# TSOC_GROVEY_WIFI_R0_0.net
KiCad netlist of a schematic drawn in EAGLE
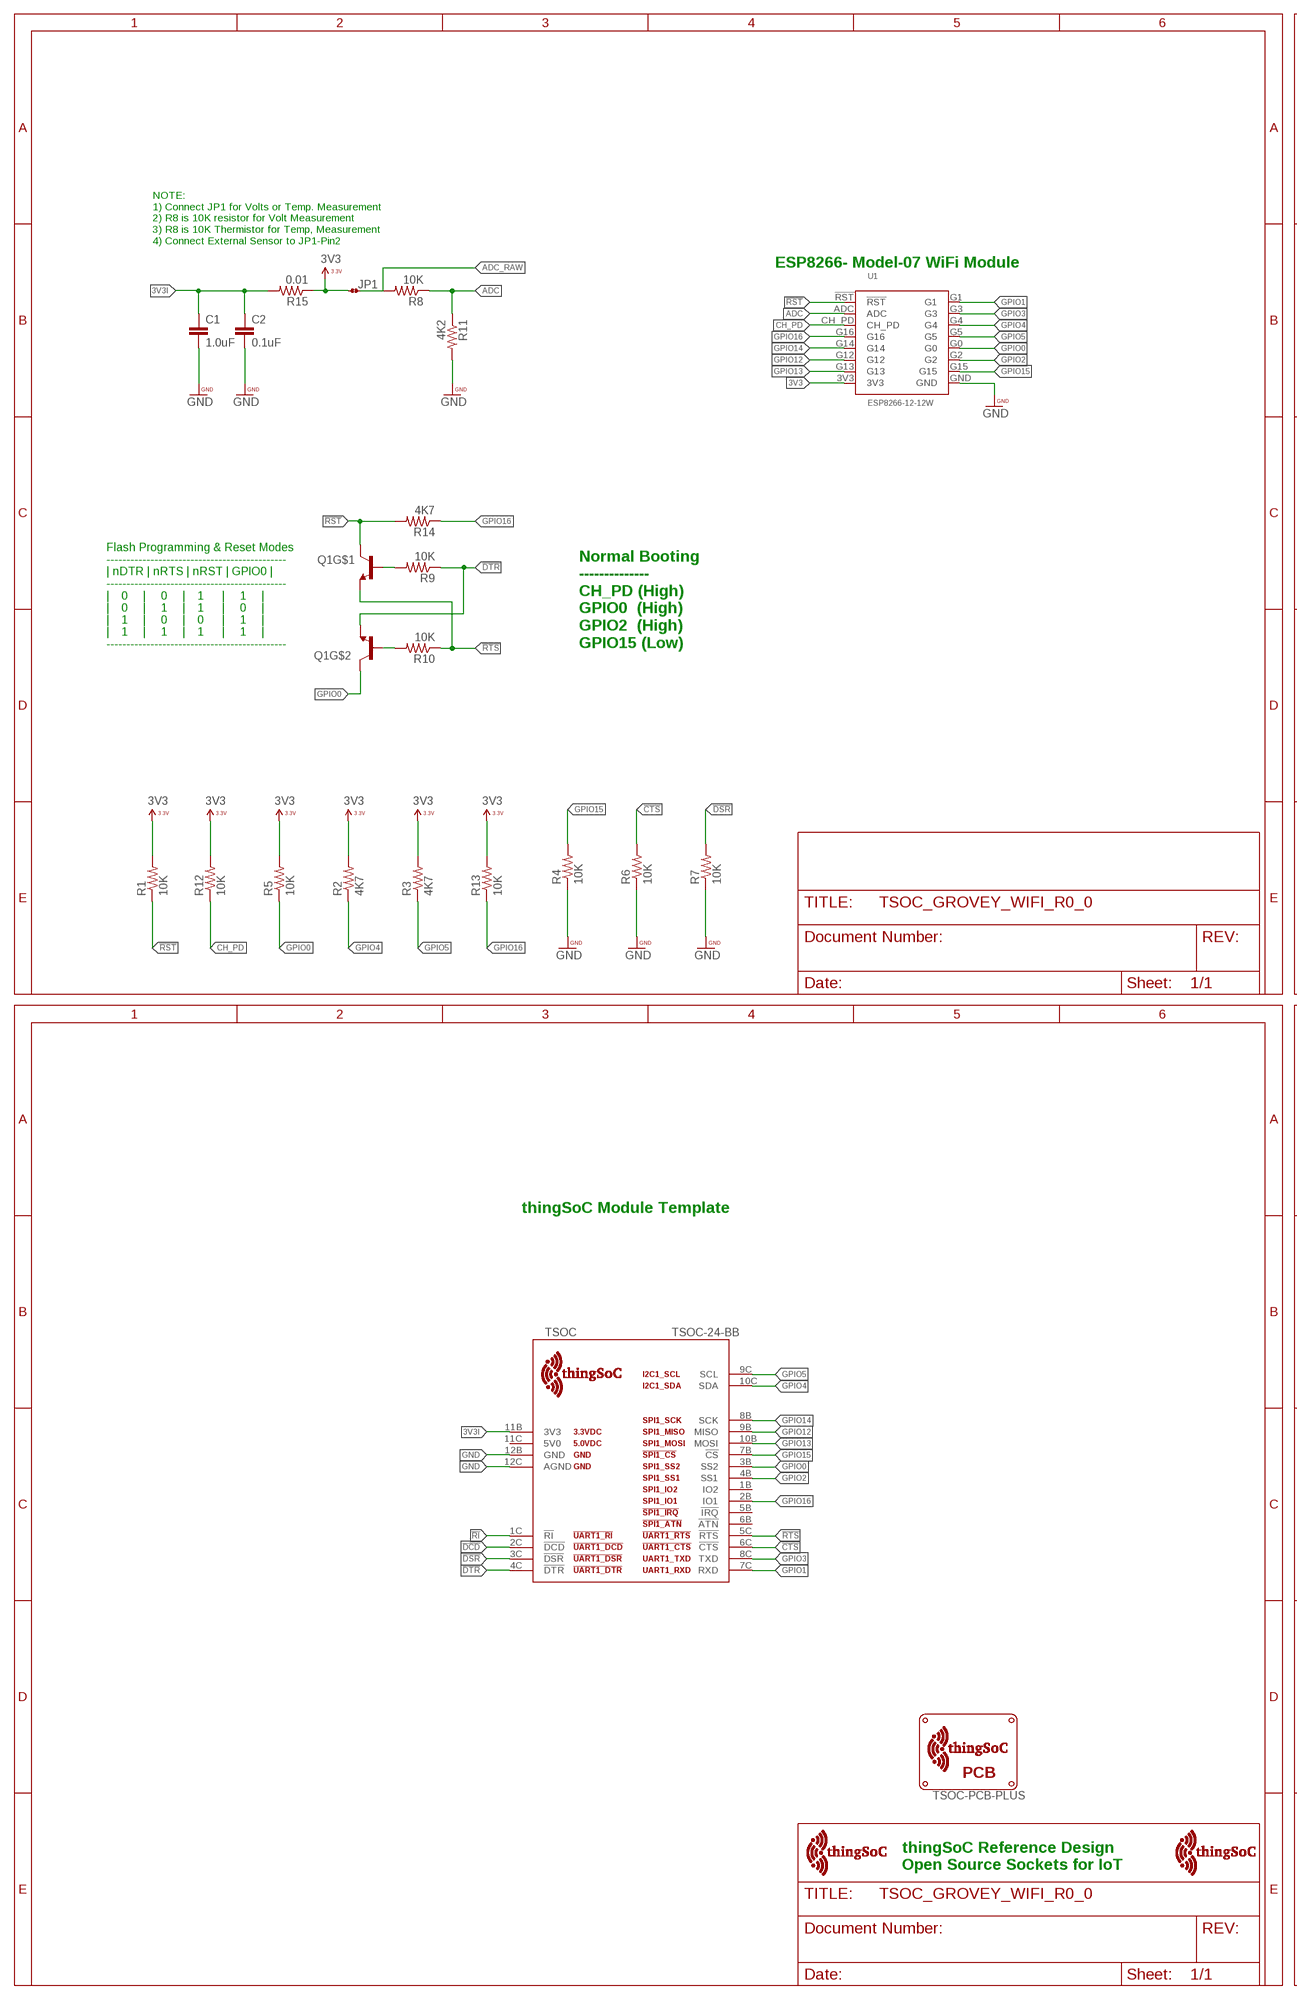
[diagram p0: schematic, sheet 1, part 1 of 2]
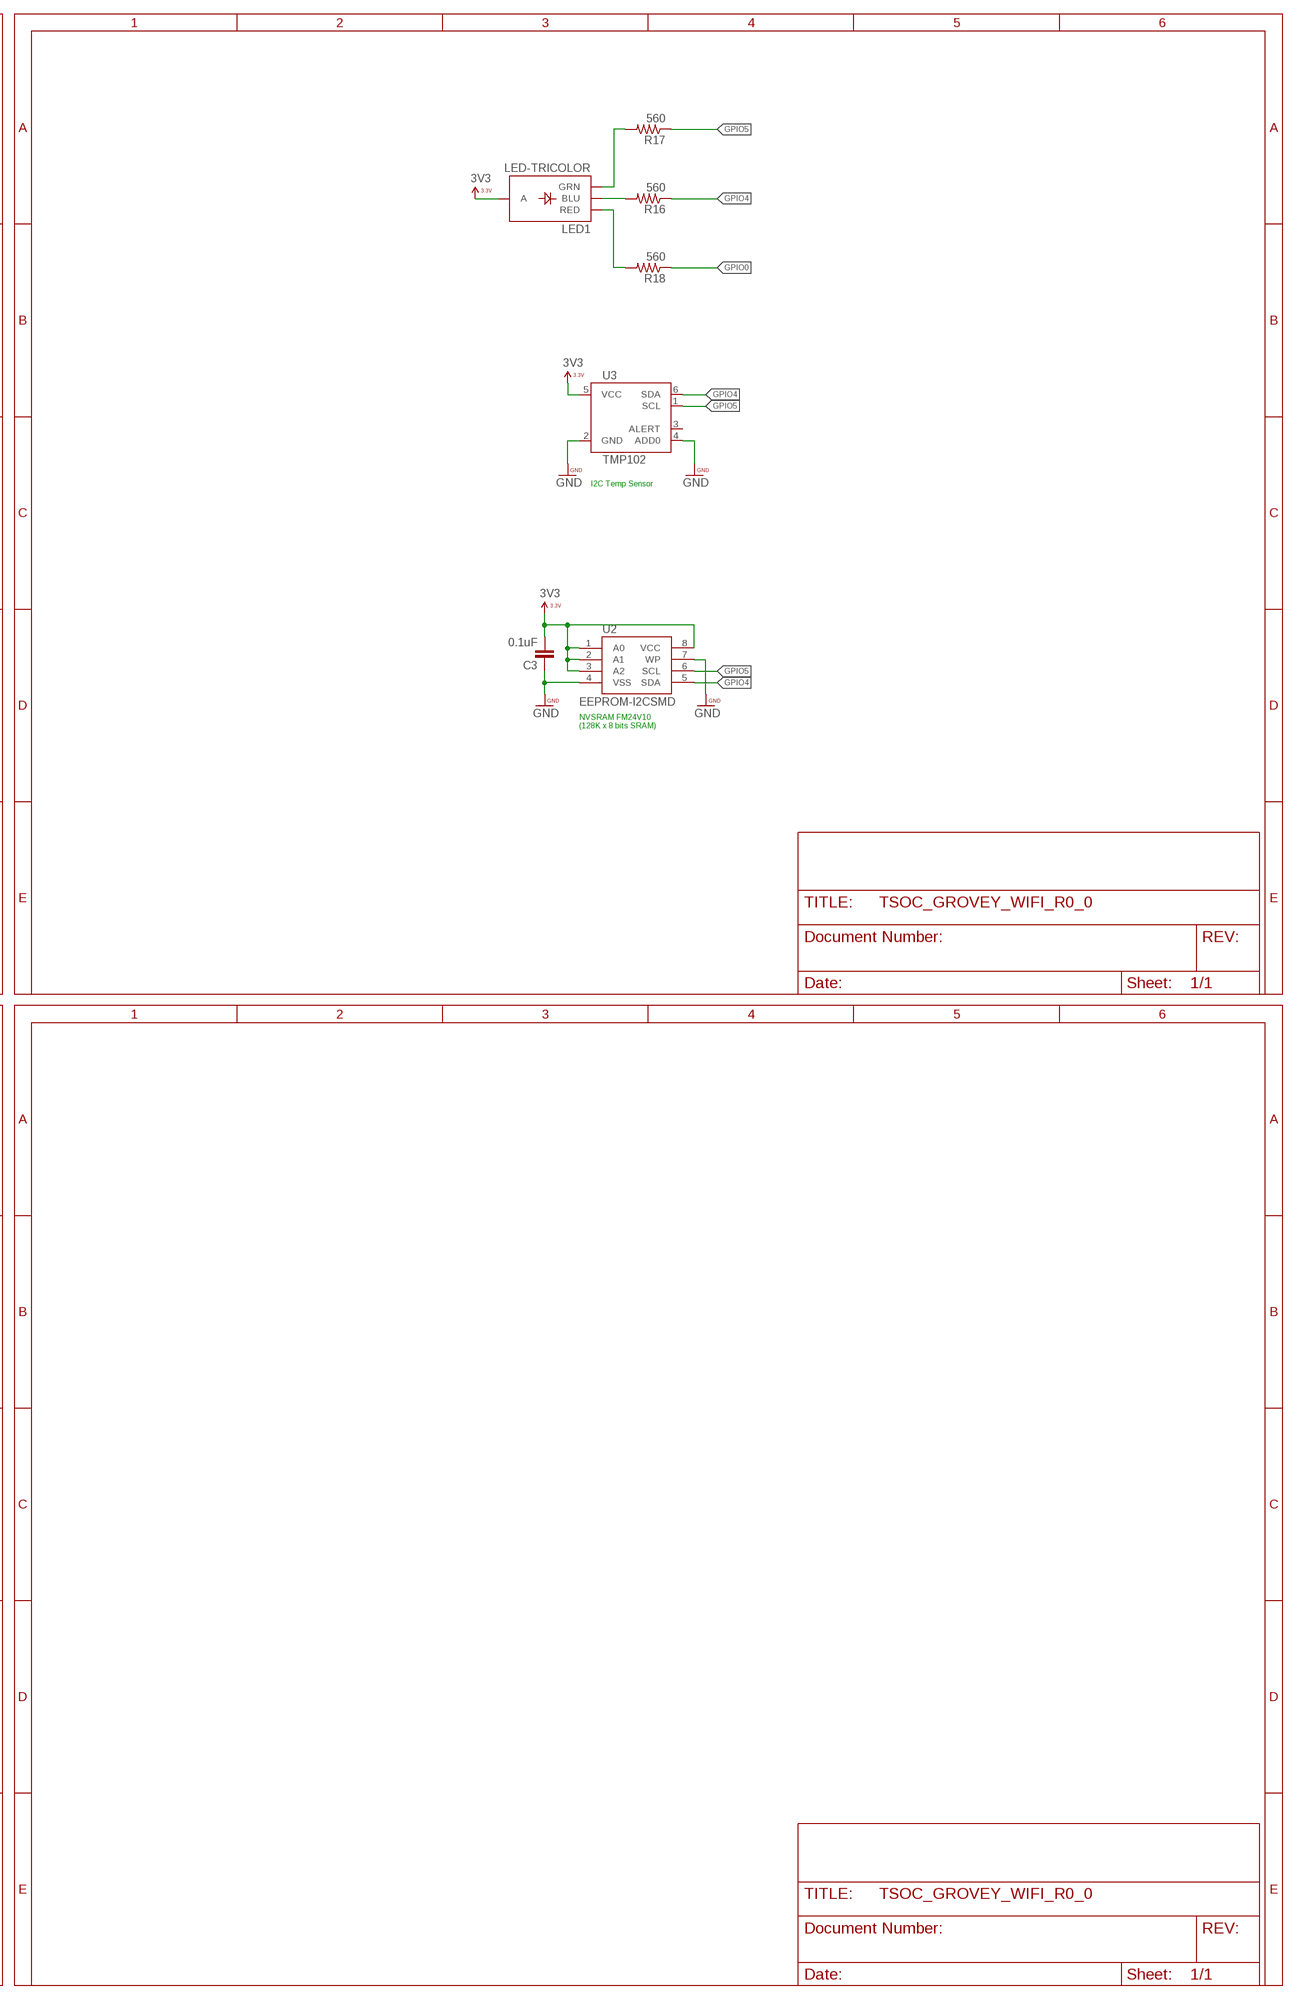
[diagram p1: schematic, sheet 1, part 2 of 2]

(export (version "E")
  (design (tool "Eeschema 10.0.6"))
  (components
    (comp (ref "C1")
      (value "1.0uF")
      (footprint "eagle-import:0402-CAP")
      (libsource (lib "eagle-import") (part "CAP0402-CAP"))
    )
    (comp (ref "C2")
      (value "0.1uF")
      (footprint "eagle-import:0402-CAP")
      (libsource (lib "eagle-import") (part "CAP0402-CAP"))
    )
    (comp (ref "C3")
      (value "0.1uF")
      (footprint "eagle-import:0402-CAP")
      (libsource (lib "eagle-import") (part "CAP0402-CAP"))
    )
    (comp (ref "JP1")
      (value "JMP-2-NO-0402")
      (footprint "eagle-import:JMP-2-NO-0402")
      (libsource (lib "eagle-import") (part "JMP-2-NO-0402"))
    )
    (comp (ref "LED1")
      (value "LED-TRICOLOR")
      (footprint "eagle-import:LED-TRICOLOR-SMD")
      (libsource (lib "eagle-import") (part "LED-TRICOLOR"))
    )
    (comp (ref "Q1")
      (value "MMBT2222A")
      (footprint "eagle-import:SOT363")
      (libsource (lib "eagle-import") (part "MMDT3904"))
    )
    (comp (ref "R1")
      (value "10K")
      (footprint "eagle-import:0402-RES")
      (libsource (lib "eagle-import") (part "RESISTOR0402"))
    )
    (comp (ref "R2")
      (value "4K7")
      (footprint "eagle-import:0402-RES")
      (libsource (lib "eagle-import") (part "RESISTOR0402"))
    )
    (comp (ref "R3")
      (value "4K7")
      (footprint "eagle-import:0402-RES")
      (libsource (lib "eagle-import") (part "RESISTOR0402"))
    )
    (comp (ref "R4")
      (value "10K")
      (footprint "eagle-import:0402-RES")
      (libsource (lib "eagle-import") (part "RESISTOR0402"))
    )
    (comp (ref "R5")
      (value "10K")
      (footprint "eagle-import:0402-RES")
      (libsource (lib "eagle-import") (part "RESISTOR0402"))
    )
    (comp (ref "R6")
      (value "10K")
      (footprint "eagle-import:0402-RES")
      (libsource (lib "eagle-import") (part "RESISTOR0402"))
    )
    (comp (ref "R7")
      (value "10K")
      (footprint "eagle-import:0402-RES")
      (libsource (lib "eagle-import") (part "RESISTOR0402"))
    )
    (comp (ref "R8")
      (value "10K")
      (footprint "eagle-import:0402-RES")
      (libsource (lib "eagle-import") (part "RESISTOR0402"))
    )
    (comp (ref "R9")
      (value "10K")
      (footprint "eagle-import:0402-RES")
      (libsource (lib "eagle-import") (part "RESISTOR0402"))
    )
    (comp (ref "R10")
      (value "10K")
      (footprint "eagle-import:0402-RES")
      (libsource (lib "eagle-import") (part "RESISTOR0402"))
    )
    (comp (ref "R11")
      (value "4K2")
      (footprint "eagle-import:0402-RES")
      (libsource (lib "eagle-import") (part "RESISTOR0402"))
    )
    (comp (ref "R12")
      (value "10K")
      (footprint "eagle-import:0402-RES")
      (libsource (lib "eagle-import") (part "RESISTOR0402"))
    )
    (comp (ref "R13")
      (value "10K")
      (footprint "eagle-import:0402-RES")
      (libsource (lib "eagle-import") (part "RESISTOR0402"))
    )
    (comp (ref "R14")
      (value "4K7")
      (footprint "eagle-import:0402-RES")
      (libsource (lib "eagle-import") (part "RESISTOR0402"))
    )
    (comp (ref "R15")
      (value "0.01")
      (footprint "eagle-import:0402-RES")
      (libsource (lib "eagle-import") (part "RESISTOR0402"))
    )
    (comp (ref "R16")
      (value "560")
      (footprint "eagle-import:0402-RES")
      (libsource (lib "eagle-import") (part "RESISTOR0402"))
    )
    (comp (ref "R17")
      (value "560")
      (footprint "eagle-import:0402-RES")
      (libsource (lib "eagle-import") (part "RESISTOR0402"))
    )
    (comp (ref "R18")
      (value "560")
      (footprint "eagle-import:0402-RES")
      (libsource (lib "eagle-import") (part "RESISTOR0402"))
    )
    (comp (ref "TSOC")
      (value "TSOC-24-BB")
      (footprint "eagle-import:TSOC-BB-S24")
      (libsource (lib "eagle-import") (part "TSOC-24-BB"))
    )
    (comp (ref "U$19")
      (value "TSOC-LOGO-MED")
      (footprint "eagle-import:TSOC-LOGO-MED")
      (libsource (lib "eagle-import") (part "TSOC-LOGO-MED"))
    )
    (comp (ref "U$20")
      (value "TSOC-LOGO-MED")
      (footprint "eagle-import:TSOC-LOGO-MED")
      (libsource (lib "eagle-import") (part "TSOC-LOGO-MED"))
    )
    (comp (ref "U$25")
      (value "TSOC-PCB-PLUS")
      (footprint "eagle-import:TSOC-BB-BRD-PLUS-DIM")
      (libsource (lib "eagle-import") (part "TSOC-PCB-PLUS"))
    )
    (comp (ref "U1")
      (value "ESP8266-12-12W")
      (footprint "eagle-import:ESP8266-12W")
      (libsource (lib "eagle-import") (part "ESP8266-12-12W"))
    )
    (comp (ref "U2")
      (value "EEPROM-I2CSMD")
      (footprint "eagle-import:SO08")
      (libsource (lib "eagle-import") (part "EEPROM-I2CSMD"))
    )
    (comp (ref "U3")
      (value "TMP102")
      (footprint "eagle-import:SOT563")
      (libsource (lib "eagle-import") (part "TMP102"))
    )
  )
  (nets
    (net (code "1") (name "/~{CTS}") (class "Default")
      (node (ref "R6") (pin "2") (pinfunction "2_2") (pintype "passive"))
      (node (ref "TSOC") (pin "6C") (pinfunction "~{CTS}_6C") (pintype "bidirectional"))
    )
    (net (code "2") (name "/~{DCD}") (class "Default")
      (node (ref "TSOC") (pin "2C") (pinfunction "~{DCD}_2C") (pintype "bidirectional"))
    )
    (net (code "3") (name "/~{DSR}") (class "Default")
      (node (ref "R7") (pin "2") (pinfunction "2_2") (pintype "passive"))
      (node (ref "TSOC") (pin "3C") (pinfunction "~{DSR}_3C") (pintype "bidirectional"))
    )
    (net (code "4") (name "/~{DTR}") (class "Default")
      (node (ref "Q1") (pin "1") (pinfunction "E_1") (pintype "passive"))
      (node (ref "R9") (pin "1") (pinfunction "1_1") (pintype "passive"))
      (node (ref "TSOC") (pin "4C") (pinfunction "~{DTR}_4C") (pintype "bidirectional"))
    )
    (net (code "5") (name "/~{RI}") (class "Default")
      (node (ref "TSOC") (pin "1C") (pinfunction "~{RI}_1C") (pintype "bidirectional"))
    )
    (net (code "6") (name "/~{RST}") (class "Default")
      (node (ref "Q1") (pin "3") (pinfunction "C_3") (pintype "passive"))
      (node (ref "R1") (pin "1") (pinfunction "1_1") (pintype "passive"))
      (node (ref "R14") (pin "2") (pinfunction "2_2") (pintype "passive"))
      (node (ref "U1") (pin "!RST") (pinfunction "~{RST}_!RST") (pintype "bidirectional"))
    )
    (net (code "7") (name "/~{RTS}") (class "Default")
      (node (ref "Q1") (pin "4") (pinfunction "E_4") (pintype "passive"))
      (node (ref "R10") (pin "1") (pinfunction "1_1") (pintype "passive"))
      (node (ref "TSOC") (pin "5C") (pinfunction "~{RTS}_5C") (pintype "bidirectional"))
    )
    (net (code "8") (name "3V3") (class "Default")
      (node (ref "C3") (pin "2") (pinfunction "2_2") (pintype "passive"))
      (node (ref "JP1") (pin "1") (pinfunction "1_1") (pintype "passive"))
      (node (ref "LED1") (pin "A") (pinfunction "A_A") (pintype "bidirectional"))
      (node (ref "R1") (pin "2") (pinfunction "2_2") (pintype "passive"))
      (node (ref "R12") (pin "2") (pinfunction "2_2") (pintype "passive"))
      (node (ref "R13") (pin "2") (pinfunction "2_2") (pintype "passive"))
      (node (ref "R15") (pin "1") (pinfunction "1_1") (pintype "passive"))
      (node (ref "R2") (pin "2") (pinfunction "2_2") (pintype "passive"))
      (node (ref "R3") (pin "2") (pinfunction "2_2") (pintype "passive"))
      (node (ref "R5") (pin "2") (pinfunction "2_2") (pintype "passive"))
      (node (ref "U1") (pin "3V3") (pinfunction "3V3_3V3") (pintype "bidirectional"))
      (node (ref "U2") (pin "1") (pinfunction "A0_1") (pintype "bidirectional"))
      (node (ref "U2") (pin "2") (pinfunction "A1_2") (pintype "bidirectional"))
      (node (ref "U2") (pin "3") (pinfunction "A2_3") (pintype "bidirectional"))
      (node (ref "U2") (pin "8") (pinfunction "VCC_8") (pintype "power_in"))
      (node (ref "U3") (pin "5") (pinfunction "VCC_5") (pintype "bidirectional"))
    )
    (net (code "9") (name "3V3I") (class "Default")
      (node (ref "C1") (pin "1") (pinfunction "1_1") (pintype "passive"))
      (node (ref "C2") (pin "1") (pinfunction "1_1") (pintype "passive"))
      (node (ref "R15") (pin "2") (pinfunction "2_2") (pintype "passive"))
      (node (ref "TSOC") (pin "11B") (pinfunction "3V3_11B") (pintype "bidirectional"))
    )
    (net (code "10") (name "ADC") (class "Default")
      (node (ref "R11") (pin "1") (pinfunction "1_1") (pintype "passive"))
      (node (ref "R8") (pin "1") (pinfunction "1_1") (pintype "passive"))
      (node (ref "U1") (pin "ADC") (pinfunction "ADC_ADC") (pintype "bidirectional"))
    )
    (net (code "11") (name "ADC_RAW") (class "Default")
      (node (ref "JP1") (pin "2") (pinfunction "2_2") (pintype "passive"))
      (node (ref "R8") (pin "2") (pinfunction "2_2") (pintype "passive"))
    )
    (net (code "12") (name "CH_PD") (class "Default")
      (node (ref "R12") (pin "1") (pinfunction "1_1") (pintype "passive"))
      (node (ref "U1") (pin "CH_PD") (pinfunction "CH_PD_CH_PD") (pintype "bidirectional"))
    )
    (net (code "13") (name "GND") (class "Default")
      (node (ref "C1") (pin "2") (pinfunction "2_2") (pintype "passive"))
      (node (ref "C2") (pin "2") (pinfunction "2_2") (pintype "passive"))
      (node (ref "C3") (pin "1") (pinfunction "1_1") (pintype "passive"))
      (node (ref "R11") (pin "2") (pinfunction "2_2") (pintype "passive"))
      (node (ref "R4") (pin "1") (pinfunction "1_1") (pintype "passive"))
      (node (ref "R6") (pin "1") (pinfunction "1_1") (pintype "passive"))
      (node (ref "R7") (pin "1") (pinfunction "1_1") (pintype "passive"))
      (node (ref "TSOC") (pin "12B") (pinfunction "GND_12B") (pintype "bidirectional"))
      (node (ref "TSOC") (pin "12C") (pinfunction "AGND_12C") (pintype "bidirectional"))
      (node (ref "U1") (pin "GND") (pinfunction "GND_GND") (pintype "bidirectional"))
      (node (ref "U2") (pin "4") (pinfunction "VSS_4") (pintype "power_in"))
      (node (ref "U2") (pin "7") (pinfunction "WP_7") (pintype "bidirectional"))
      (node (ref "U3") (pin "2") (pinfunction "GND_2") (pintype "bidirectional"))
      (node (ref "U3") (pin "4") (pinfunction "ADD0_4") (pintype "bidirectional"))
    )
    (net (code "14") (name "GPIO0") (class "Default")
      (node (ref "Q1") (pin "6") (pinfunction "C_6") (pintype "passive"))
      (node (ref "R18") (pin "1") (pinfunction "1_1") (pintype "passive"))
      (node (ref "R5") (pin "1") (pinfunction "1_1") (pintype "passive"))
      (node (ref "TSOC") (pin "3B") (pinfunction "SS2_3B") (pintype "bidirectional"))
      (node (ref "U1") (pin "G0") (pinfunction "G0_G0") (pintype "bidirectional"))
    )
    (net (code "15") (name "GPIO1") (class "Default")
      (node (ref "TSOC") (pin "7C") (pinfunction "RXD_7C") (pintype "bidirectional"))
      (node (ref "U1") (pin "G1") (pinfunction "G1_G1") (pintype "bidirectional"))
    )
    (net (code "16") (name "GPIO2") (class "Default")
      (node (ref "TSOC") (pin "4B") (pinfunction "SS1_4B") (pintype "bidirectional"))
      (node (ref "U1") (pin "G2") (pinfunction "G2_G2") (pintype "bidirectional"))
    )
    (net (code "17") (name "GPIO3") (class "Default")
      (node (ref "TSOC") (pin "8C") (pinfunction "TXD_8C") (pintype "bidirectional"))
      (node (ref "U1") (pin "G3") (pinfunction "G3_G3") (pintype "bidirectional"))
    )
    (net (code "18") (name "GPIO4") (class "Default")
      (node (ref "R16") (pin "1") (pinfunction "1_1") (pintype "passive"))
      (node (ref "R2") (pin "1") (pinfunction "1_1") (pintype "passive"))
      (node (ref "TSOC") (pin "10C") (pinfunction "SDA_10C") (pintype "bidirectional"))
      (node (ref "U1") (pin "G4") (pinfunction "G4_G4") (pintype "bidirectional"))
      (node (ref "U2") (pin "5") (pinfunction "SDA_5") (pintype "bidirectional"))
      (node (ref "U3") (pin "6") (pinfunction "SDA_6") (pintype "bidirectional"))
    )
    (net (code "19") (name "GPIO5") (class "Default")
      (node (ref "R17") (pin "1") (pinfunction "1_1") (pintype "passive"))
      (node (ref "R3") (pin "1") (pinfunction "1_1") (pintype "passive"))
      (node (ref "TSOC") (pin "9C") (pinfunction "SCL_9C") (pintype "bidirectional"))
      (node (ref "U1") (pin "G5") (pinfunction "G5_G5") (pintype "bidirectional"))
      (node (ref "U2") (pin "6") (pinfunction "SCL_6") (pintype "bidirectional"))
      (node (ref "U3") (pin "1") (pinfunction "SCL_1") (pintype "bidirectional"))
    )
    (net (code "20") (name "GPIO12") (class "Default")
      (node (ref "TSOC") (pin "9B") (pinfunction "MISO_9B") (pintype "bidirectional"))
      (node (ref "U1") (pin "G12") (pinfunction "G12_G12") (pintype "bidirectional"))
    )
    (net (code "21") (name "GPIO13") (class "Default")
      (node (ref "TSOC") (pin "10B") (pinfunction "MOSI_10B") (pintype "bidirectional"))
      (node (ref "U1") (pin "G13") (pinfunction "G13_G13") (pintype "bidirectional"))
    )
    (net (code "22") (name "GPIO14") (class "Default")
      (node (ref "TSOC") (pin "8B") (pinfunction "SCK_8B") (pintype "bidirectional"))
      (node (ref "U1") (pin "G14") (pinfunction "G14_G14") (pintype "bidirectional"))
    )
    (net (code "23") (name "GPIO15") (class "Default")
      (node (ref "R4") (pin "2") (pinfunction "2_2") (pintype "passive"))
      (node (ref "TSOC") (pin "7B") (pinfunction "~{CS}_7B") (pintype "bidirectional"))
      (node (ref "U1") (pin "G15") (pinfunction "G15_G15") (pintype "bidirectional"))
    )
    (net (code "24") (name "GPIO16") (class "Default")
      (node (ref "R13") (pin "1") (pinfunction "1_1") (pintype "passive"))
      (node (ref "R14") (pin "1") (pinfunction "1_1") (pintype "passive"))
      (node (ref "TSOC") (pin "2B") (pinfunction "IO1_2B") (pintype "bidirectional"))
      (node (ref "U1") (pin "G16") (pinfunction "G16_G16") (pintype "bidirectional"))
    )
    (net (code "25") (name "Net-(LED1-BLU)") (class "Default")
      (node (ref "LED1") (pin "B") (pinfunction "BLU_B") (pintype "bidirectional"))
      (node (ref "R16") (pin "2") (pinfunction "2_2") (pintype "passive"))
    )
    (net (code "26") (name "Net-(LED1-GRN)") (class "Default")
      (node (ref "LED1") (pin "G") (pinfunction "GRN_G") (pintype "bidirectional"))
      (node (ref "R17") (pin "2") (pinfunction "2_2") (pintype "passive"))
    )
    (net (code "27") (name "Net-(LED1-RED)") (class "Default")
      (node (ref "LED1") (pin "R") (pinfunction "RED_R") (pintype "bidirectional"))
      (node (ref "R18") (pin "2") (pinfunction "2_2") (pintype "passive"))
    )
    (net (code "28") (name "Net-(Q1A-B)") (class "Default")
      (node (ref "Q1") (pin "5") (pinfunction "B_5") (pintype "passive"))
      (node (ref "R9") (pin "2") (pinfunction "2_2") (pintype "passive"))
    )
    (net (code "29") (name "Net-(Q1B-B)") (class "Default")
      (node (ref "Q1") (pin "2") (pinfunction "B_2") (pintype "passive"))
      (node (ref "R10") (pin "2") (pinfunction "2_2") (pintype "passive"))
    )
    (net (code "30") (name "unconnected-(TSOC-5V0-Pad11C)") (class "Default")
      (node (ref "TSOC") (pin "11C") (pinfunction "5V0_11C") (pintype "bidirectional"))
    )
    (net (code "31") (name "unconnected-(TSOC-IO2-Pad1B)") (class "Default")
      (node (ref "TSOC") (pin "1B") (pinfunction "IO2_1B") (pintype "bidirectional"))
    )
    (net (code "32") (name "unconnected-(TSOC-~{ATN}-Pad6B)") (class "Default")
      (node (ref "TSOC") (pin "6B") (pinfunction "~{ATN}_6B") (pintype "bidirectional"))
    )
    (net (code "33") (name "unconnected-(TSOC-~{IRQ}-Pad5B)") (class "Default")
      (node (ref "TSOC") (pin "5B") (pinfunction "~{IRQ}_5B") (pintype "bidirectional"))
    )
    (net (code "34") (name "unconnected-(U3-ALERT-Pad3)") (class "Default")
      (node (ref "U3") (pin "3") (pinfunction "ALERT_3") (pintype "bidirectional"))
    )
  )
)
